# SCH_LED-Chasing-PCB_2025-11-02.net
KiCad netlist of a schematic drawn in EasyEDA
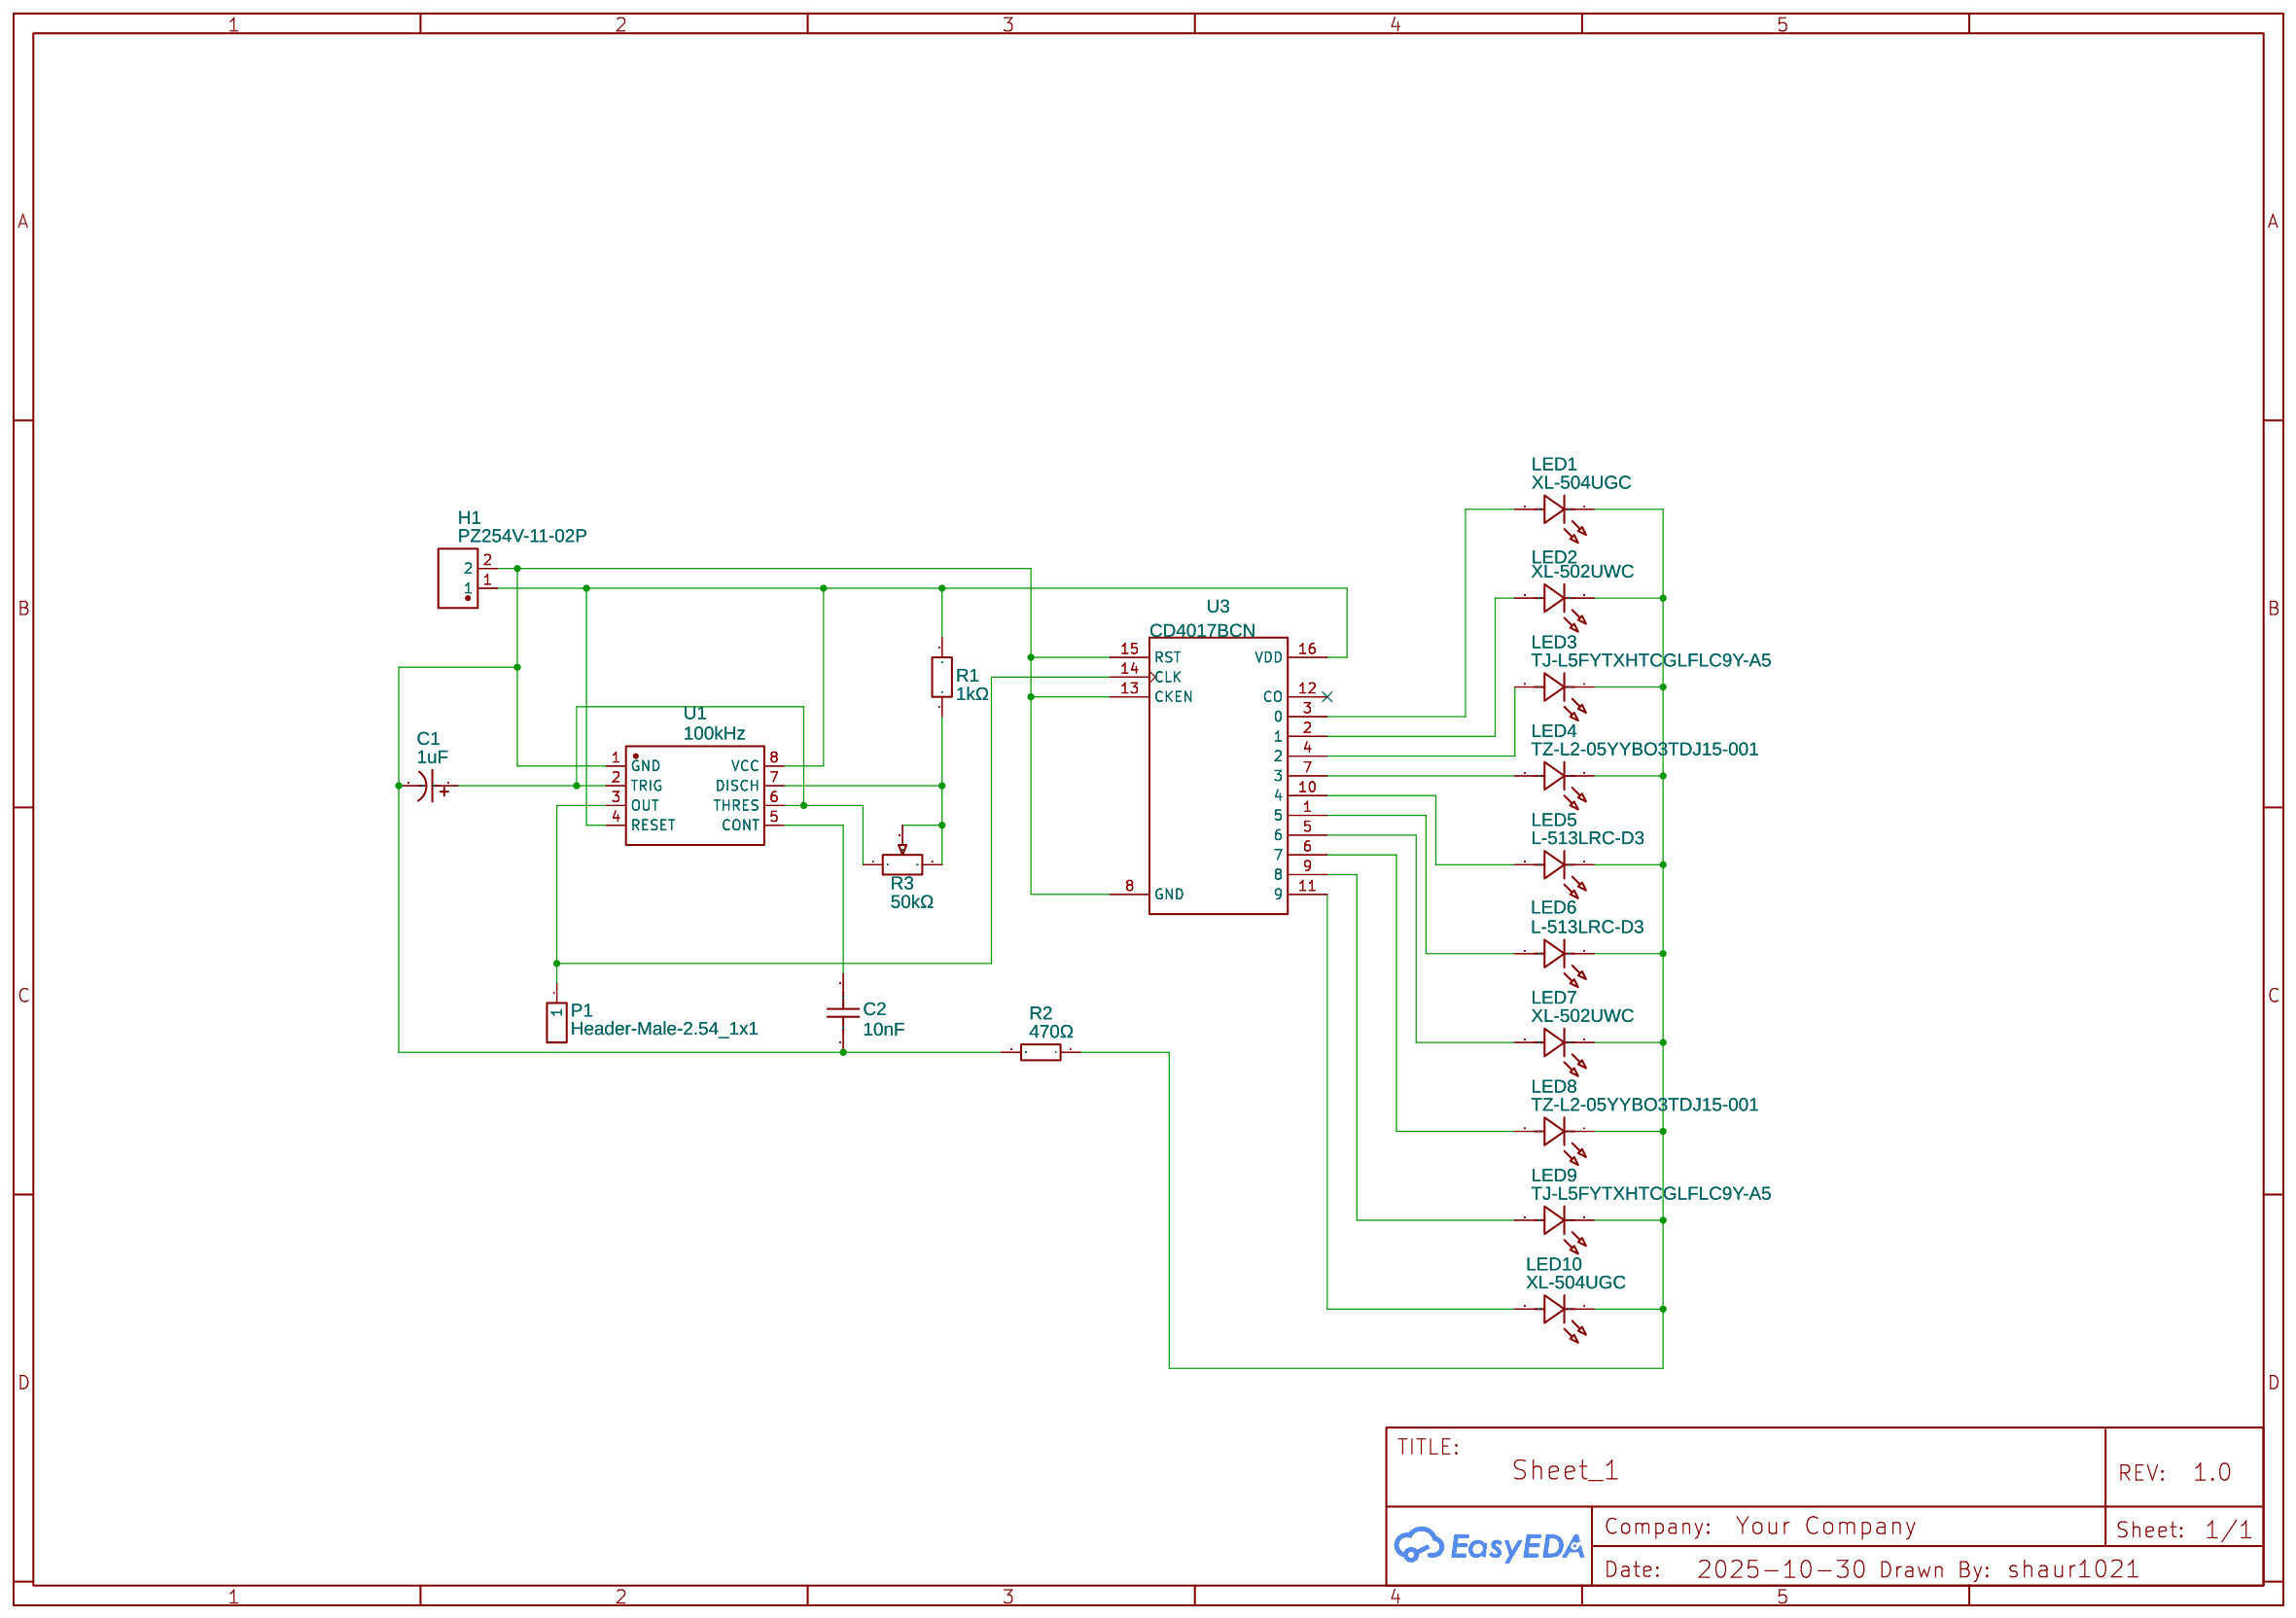
[diagram p0: schematic sheet]

(export (version "E")
  (design (tool "Eeschema 10.0.6"))
  (components
    (comp (ref "C1")
      (value "1uF")
      (fields (field (name "Manufacturer Part") "KF010M050C110A") (field (name "Manufacturer") "CapXon(丰宾)"))
      (libsource (lib "") (part "KF010M050C110A"))
    )
    (comp (ref "C2")
      (value "10nF")
      (fields (field (name "Manufacturer Part") "N09F1B103MN0B0S0N0") (field (name "Manufacturer") "STE(松田)"))
      (libsource (lib "") (part "N09F1B103MN0B0S0N0"))
    )
    (comp (ref "H1")
      (value "PZ254V-11-02P")
      (fields (field (name "Manufacturer") "XFCN(兴飞)"))
      (libsource (lib "") (part "PZ254V-11-02P"))
    )
    (comp (ref "LED1")
      (value "XL-504UGC")
      (fields (field (name "Manufacturer") "XINGLIGHT(成兴光)"))
      (libsource (lib "") (part "XL-504UGC"))
    )
    (comp (ref "LED2")
      (value "XL-502UWC")
      (fields (field (name "Manufacturer") "XINGLIGHT(成兴光)"))
      (libsource (lib "") (part "XL-502UWC"))
    )
    (comp (ref "LED3")
      (value "TJ-L5FYTXHTCGLFLC9Y-A5")
      (fields (field (name "Manufacturer") "TOGIALED(统佳)"))
      (libsource (lib "") (part "TJ-L5FYTXHTCGLFLC9Y-A5"))
    )
    (comp (ref "LED4")
      (value "TZ-L2-05YYBO3TDJ15-001")
      (fields (field (name "Manufacturer") "TUOZHAN(拓展光电)"))
      (libsource (lib "") (part "TZ-L2-05YYBO3TDJ15-001"))
    )
    (comp (ref "LED5")
      (value "L-513LRC-D3")
      (fields (field (name "Manufacturer") "PARALIGHT(光鼎)"))
      (libsource (lib "") (part "L-513LRC-D3"))
    )
    (comp (ref "LED6")
      (value "L-513LRC-D3")
      (fields (field (name "Manufacturer") "PARALIGHT(光鼎)"))
      (libsource (lib "") (part "L-513LRC-D3"))
    )
    (comp (ref "LED7")
      (value "XL-502UWC")
      (fields (field (name "Manufacturer") "XINGLIGHT(成兴光)"))
      (libsource (lib "") (part "XL-502UWC"))
    )
    (comp (ref "LED8")
      (value "TZ-L2-05YYBO3TDJ15-001")
      (fields (field (name "Manufacturer") "TUOZHAN(拓展光电)"))
      (libsource (lib "") (part "TZ-L2-05YYBO3TDJ15-001"))
    )
    (comp (ref "LED9")
      (value "TJ-L5FYTXHTCGLFLC9Y-A5")
      (fields (field (name "Manufacturer") "TOGIALED(统佳)"))
      (libsource (lib "") (part "TJ-L5FYTXHTCGLFLC9Y-A5"))
    )
    (comp (ref "LED10")
      (value "XL-504UGC")
      (fields (field (name "Manufacturer") "XINGLIGHT(成兴光)"))
      (libsource (lib "") (part "XL-504UGC"))
    )
    (comp (ref "P1")
      (value "Header-Male-2.54_1x1")
      (fields (field (name "Manufacturer Part") "2.54-1*1P针") (field (name "Manufacturer") "BOOMELE(博穆精密)"))
      (libsource (lib "") (part "Header-Male-2.54_1x1"))
    )
    (comp (ref "R1")
      (value "1kΩ")
      (fields (field (name "Manufacturer Part") "MF1/4W-1KΩ±1%T52") (field (name "Manufacturer") "华星机电"))
      (libsource (lib "") (part "MF1/4W-1KΩ±1%T52"))
    )
    (comp (ref "R2")
      (value "470Ω")
      (fields
        (field (name "Manufacturer Part") "MFR0W4F4700A50")
        (field (name "Manufacturer") "UNI-ROYAL(厚声)")
      )
      (libsource (lib "") (part "MFR0W4F4700A50"))
    )
    (comp (ref "R3")
      (value "50kΩ")
      (fields (field (name "Manufacturer Part") "3296X-1-503") (field (name "Manufacturer") "BOCHEN(博晨)"))
      (libsource (lib "") (part "3296X-1-503_C118912"))
    )
    (comp (ref "U1")
      (value "100kHz")
      (fields (field (name "Manufacturer Part") "NE555P") (field (name "Manufacturer") "TI(德州仪器)"))
      (libsource (lib "") (part "NE555P"))
    )
    (comp (ref "U3") (value "CD4017BCN") (libsource (lib "") (part "CD4017BCN")))
  )
  (nets
    (net (code "1") (name "Net-(LED1-A)") (class "Default")
      (node (ref "LED1") (pin "2") (pinfunction "A_2") (pintype "unspecified"))
      (node (ref "U3") (pin "3") (pinfunction "0_3") (pintype "output"))
    )
    (net (code "2") (name "Net-(LED1-K)") (class "Default")
      (node (ref "LED1") (pin "1") (pinfunction "K_1") (pintype "unspecified"))
      (node (ref "LED10") (pin "1") (pinfunction "K_1") (pintype "unspecified"))
      (node (ref "LED2") (pin "1") (pinfunction "K_1") (pintype "unspecified"))
      (node (ref "LED3") (pin "1") (pinfunction "-_1") (pintype "unspecified"))
      (node (ref "LED4") (pin "1") (pinfunction "-_1") (pintype "unspecified"))
      (node (ref "LED5") (pin "1") (pinfunction "K_1") (pintype "unspecified"))
      (node (ref "LED6") (pin "1") (pinfunction "K_1") (pintype "unspecified"))
      (node (ref "LED7") (pin "1") (pinfunction "K_1") (pintype "unspecified"))
      (node (ref "LED8") (pin "1") (pinfunction "-_1") (pintype "unspecified"))
      (node (ref "LED9") (pin "1") (pinfunction "-_1") (pintype "unspecified"))
      (node (ref "R2") (pin "1") (pinfunction "1_1") (pintype "input"))
    )
    (net (code "3") (name "Net-(LED2-A)") (class "Default")
      (node (ref "LED2") (pin "2") (pinfunction "A_2") (pintype "unspecified"))
      (node (ref "U3") (pin "2") (pinfunction "1_2") (pintype "output"))
    )
    (net (code "4") (name "Net-(LED3-+)") (class "Default")
      (node (ref "LED3") (pin "2") (pinfunction "+_2") (pintype "unspecified"))
      (node (ref "U3") (pin "4") (pinfunction "2_4") (pintype "output"))
    )
    (net (code "5") (name "Net-(LED4-+)") (class "Default")
      (node (ref "LED4") (pin "2") (pinfunction "+_2") (pintype "unspecified"))
      (node (ref "U3") (pin "7") (pinfunction "3_7") (pintype "output"))
    )
    (net (code "6") (name "Net-(LED5-A)") (class "Default")
      (node (ref "LED5") (pin "2") (pinfunction "A_2") (pintype "unspecified"))
      (node (ref "U3") (pin "10") (pinfunction "4_10") (pintype "output"))
    )
    (net (code "7") (name "Net-(LED6-A)") (class "Default")
      (node (ref "LED6") (pin "2") (pinfunction "A_2") (pintype "unspecified"))
      (node (ref "U3") (pin "1") (pinfunction "5_1") (pintype "output"))
    )
    (net (code "8") (name "Net-(LED7-A)") (class "Default")
      (node (ref "LED7") (pin "2") (pinfunction "A_2") (pintype "unspecified"))
      (node (ref "U3") (pin "5") (pinfunction "6_5") (pintype "output"))
    )
    (net (code "9") (name "Net-(LED8-+)") (class "Default")
      (node (ref "LED8") (pin "2") (pinfunction "+_2") (pintype "unspecified"))
      (node (ref "U3") (pin "6") (pinfunction "7_6") (pintype "output"))
    )
    (net (code "10") (name "Net-(LED9-+)") (class "Default")
      (node (ref "LED9") (pin "2") (pinfunction "+_2") (pintype "unspecified"))
      (node (ref "U3") (pin "9") (pinfunction "8_9") (pintype "output"))
    )
    (net (code "11") (name "Net-(LED10-A)") (class "Default")
      (node (ref "LED10") (pin "2") (pinfunction "A_2") (pintype "unspecified"))
      (node (ref "U3") (pin "11") (pinfunction "9_11") (pintype "output"))
    )
    (net (code "12") (name "Net-(U1-CONT)") (class "Default")
      (node (ref "C2") (pin "2") (pinfunction "2_2") (pintype "unspecified"))
      (node (ref "U1") (pin "5") (pinfunction "CONT_5") (pintype "unspecified"))
    )
    (net (code "13") (name "Net-(U1-DISCH)") (class "Default")
      (node (ref "R1") (pin "1") (pinfunction "1_1") (pintype "unspecified"))
      (node (ref "R3") (pin "2") (pinfunction "2_2") (pintype "input"))
      (node (ref "R3") (pin "3") (pinfunction "3_3") (pintype "input"))
      (node (ref "U1") (pin "7") (pinfunction "DISCH_7") (pintype "unspecified"))
    )
    (net (code "14") (name "Net-(U1-GND)") (class "Default")
      (node (ref "C1") (pin "2") (pinfunction "2_2") (pintype "input"))
      (node (ref "C2") (pin "1") (pinfunction "1_1") (pintype "unspecified"))
      (node (ref "H1") (pin "2") (pinfunction "2_2") (pintype "unspecified"))
      (node (ref "R2") (pin "2") (pinfunction "2_2") (pintype "input"))
      (node (ref "U1") (pin "1") (pinfunction "GND_1") (pintype "unspecified"))
      (node (ref "U3") (pin "13") (pinfunction "CKEN_13") (pintype "unspecified"))
      (node (ref "U3") (pin "15") (pinfunction "RST_15") (pintype "unspecified"))
      (node (ref "U3") (pin "8") (pinfunction "GND_8") (pintype "passive"))
    )
    (net (code "15") (name "Net-(U1-OUT)") (class "Default")
      (node (ref "P1") (pin "1") (pinfunction "1_1") (pintype "input"))
      (node (ref "U1") (pin "3") (pinfunction "OUT_3") (pintype "unspecified"))
      (node (ref "U3") (pin "14") (pinfunction "CLK_14") (pintype "unspecified"))
    )
    (net (code "16") (name "Net-(U1-RESET)") (class "Default")
      (node (ref "H1") (pin "1") (pinfunction "1_1") (pintype "unspecified"))
      (node (ref "R1") (pin "2") (pinfunction "2_2") (pintype "unspecified"))
      (node (ref "U1") (pin "4") (pinfunction "RESET_4") (pintype "unspecified"))
      (node (ref "U1") (pin "8") (pinfunction "VCC_8") (pintype "unspecified"))
      (node (ref "U3") (pin "16") (pinfunction "VDD_16") (pintype "passive"))
    )
    (net (code "17") (name "Net-(U1-THRES)") (class "Default")
      (node (ref "C1") (pin "1") (pinfunction "1_1") (pintype "input"))
      (node (ref "R3") (pin "1") (pinfunction "1_1") (pintype "input"))
      (node (ref "U1") (pin "2") (pinfunction "TRIG_2") (pintype "unspecified"))
      (node (ref "U1") (pin "6") (pinfunction "THRES_6") (pintype "unspecified"))
    )
    (net (code "18") (name "unconnected-(U3-CO-Pad12)") (class "Default")
      (node (ref "U3") (pin "12") (pinfunction "CO_12") (pintype "output+no_connect"))
    )
  )
)
